# MTL_BaroTact1D_V3.net
KiCad netlist of a schematic drawn in EAGLE
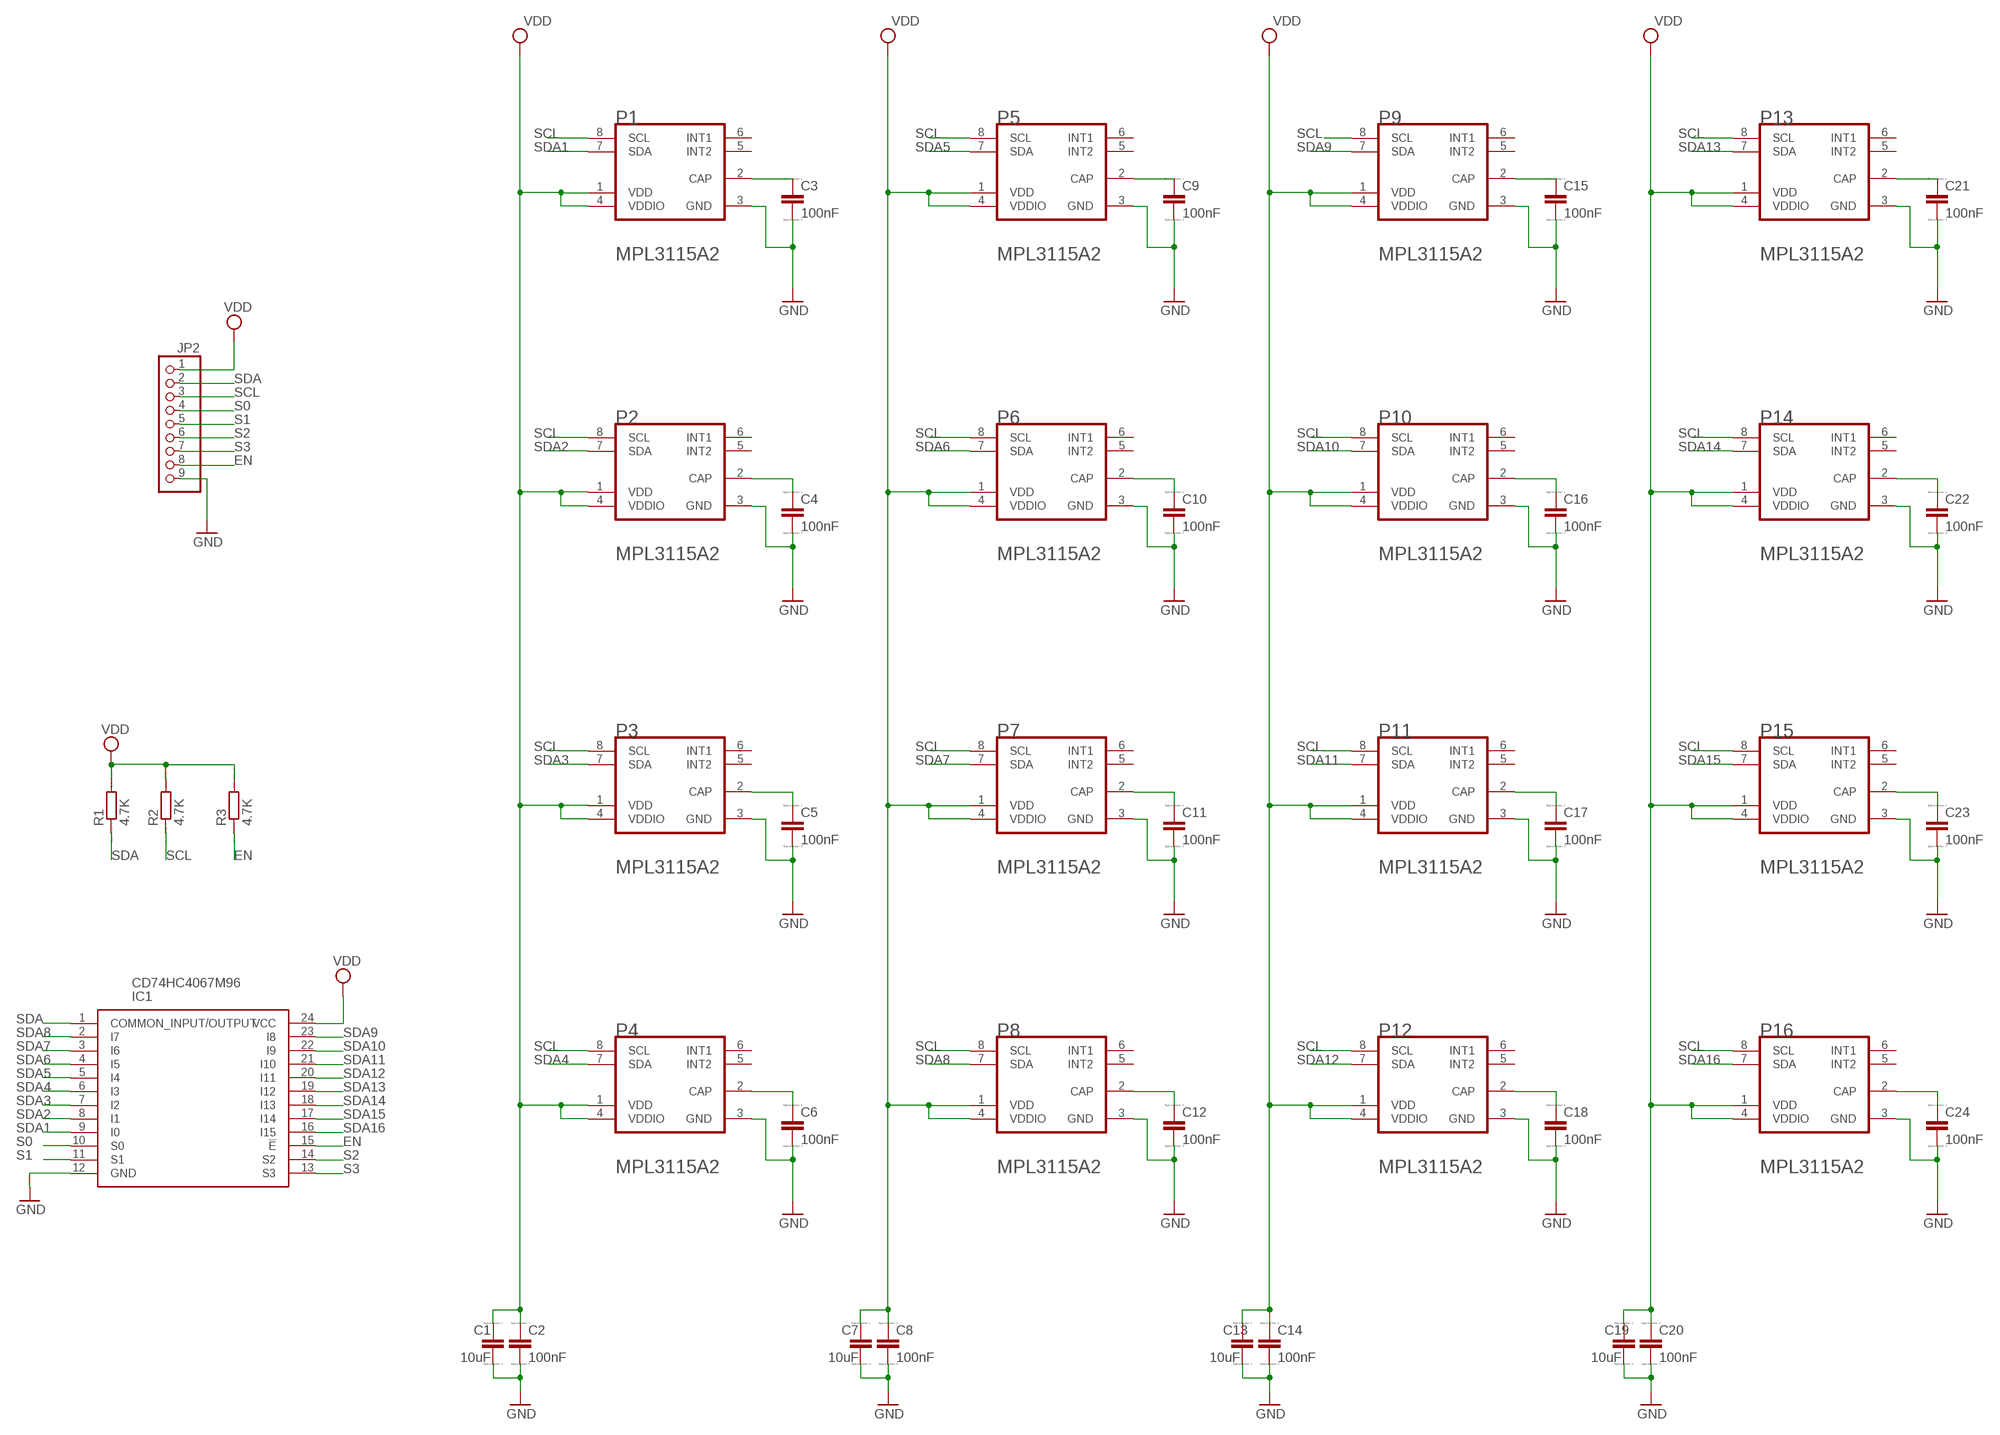
[diagram p0: schematic, sheet 1]

(export (version "E")
  (design (tool "Eeschema 10.0.6"))
  (components
    (comp (ref "C1")
      (value "10uF")
      (footprint "eagle-import:C0603")
      (libsource (lib "eagle-import") (part "CC0603"))
    )
    (comp (ref "C2")
      (value "100nF")
      (footprint "eagle-import:C0603")
      (libsource (lib "eagle-import") (part "CC0603"))
    )
    (comp (ref "C3")
      (value "100nF")
      (footprint "eagle-import:C0603")
      (libsource (lib "eagle-import") (part "CC0603"))
    )
    (comp (ref "C4")
      (value "100nF")
      (footprint "eagle-import:C0603")
      (libsource (lib "eagle-import") (part "CC0603"))
    )
    (comp (ref "C5")
      (value "100nF")
      (footprint "eagle-import:C0603")
      (libsource (lib "eagle-import") (part "CC0603"))
    )
    (comp (ref "C6")
      (value "100nF")
      (footprint "eagle-import:C0603")
      (libsource (lib "eagle-import") (part "CC0603"))
    )
    (comp (ref "C7")
      (value "10uF")
      (footprint "eagle-import:C0603")
      (libsource (lib "eagle-import") (part "CC0603"))
    )
    (comp (ref "C8")
      (value "100nF")
      (footprint "eagle-import:C0603")
      (libsource (lib "eagle-import") (part "CC0603"))
    )
    (comp (ref "C9")
      (value "100nF")
      (footprint "eagle-import:C0603")
      (libsource (lib "eagle-import") (part "CC0603"))
    )
    (comp (ref "C10")
      (value "100nF")
      (footprint "eagle-import:C0603")
      (libsource (lib "eagle-import") (part "CC0603"))
    )
    (comp (ref "C11")
      (value "100nF")
      (footprint "eagle-import:C0603")
      (libsource (lib "eagle-import") (part "CC0603"))
    )
    (comp (ref "C12")
      (value "100nF")
      (footprint "eagle-import:C0603")
      (libsource (lib "eagle-import") (part "CC0603"))
    )
    (comp (ref "C13")
      (value "10uF")
      (footprint "eagle-import:C0603")
      (libsource (lib "eagle-import") (part "CC0603"))
    )
    (comp (ref "C14")
      (value "100nF")
      (footprint "eagle-import:C0603")
      (libsource (lib "eagle-import") (part "CC0603"))
    )
    (comp (ref "C15")
      (value "100nF")
      (footprint "eagle-import:C0603")
      (libsource (lib "eagle-import") (part "CC0603"))
    )
    (comp (ref "C16")
      (value "100nF")
      (footprint "eagle-import:C0603")
      (libsource (lib "eagle-import") (part "CC0603"))
    )
    (comp (ref "C17")
      (value "100nF")
      (footprint "eagle-import:C0603")
      (libsource (lib "eagle-import") (part "CC0603"))
    )
    (comp (ref "C18")
      (value "100nF")
      (footprint "eagle-import:C0603")
      (libsource (lib "eagle-import") (part "CC0603"))
    )
    (comp (ref "C19")
      (value "10uF")
      (footprint "eagle-import:C0603")
      (libsource (lib "eagle-import") (part "CC0603"))
    )
    (comp (ref "C20")
      (value "100nF")
      (footprint "eagle-import:C0603")
      (libsource (lib "eagle-import") (part "CC0603"))
    )
    (comp (ref "C21")
      (value "100nF")
      (footprint "eagle-import:C0603")
      (libsource (lib "eagle-import") (part "CC0603"))
    )
    (comp (ref "C22")
      (value "100nF")
      (footprint "eagle-import:C0603")
      (libsource (lib "eagle-import") (part "CC0603"))
    )
    (comp (ref "C23")
      (value "100nF")
      (footprint "eagle-import:C0603")
      (libsource (lib "eagle-import") (part "CC0603"))
    )
    (comp (ref "C24")
      (value "100nF")
      (footprint "eagle-import:C0603")
      (libsource (lib "eagle-import") (part "CC0603"))
    )
    (comp (ref "IC1")
      (value "CD74HC4067M96")
      (footprint "eagle-import:SOIC127P1030X265-24N")
      (fields (field (name "MOUSER_PART_NUMBER") "595-CD74HC4067M96"))
      (libsource (lib "eagle-import") (part "CD74HC4067M96"))
    )
    (comp (ref "JP2")
      (value "PINHD-1X9")
      (footprint "eagle-import:1X09")
      (libsource (lib "eagle-import") (part "PINHD-1X9"))
    )
    (comp (ref "P1")
      (value "FREESCALE_SEMICONDUCTOR_MPL3115A2FREESCALE_SEMICONDUCTOR_MPL3115A2_0_0")
      (footprint "eagle-import:FREESCALE_SEMICONDUCTOR_MPL3115A2_0")
      (fields (field (name "MF") "Freescale Semiconductor") (field (name "MPN") "MPL3115A2"))
      (libsource (lib "eagle-import") (part "FREESCALE_SEMICONDUCTOR_MPL3115A2FREESCALE_SEMICONDUCTOR_MPL3115A2_0_0"))
    )
    (comp (ref "P2")
      (value "FREESCALE_SEMICONDUCTOR_MPL3115A2FREESCALE_SEMICONDUCTOR_MPL3115A2_0_0")
      (footprint "eagle-import:FREESCALE_SEMICONDUCTOR_MPL3115A2_0")
      (fields (field (name "MF") "Freescale Semiconductor") (field (name "MPN") "MPL3115A2"))
      (libsource (lib "eagle-import") (part "FREESCALE_SEMICONDUCTOR_MPL3115A2FREESCALE_SEMICONDUCTOR_MPL3115A2_0_0"))
    )
    (comp (ref "P3")
      (value "FREESCALE_SEMICONDUCTOR_MPL3115A2FREESCALE_SEMICONDUCTOR_MPL3115A2_0_0")
      (footprint "eagle-import:FREESCALE_SEMICONDUCTOR_MPL3115A2_0")
      (fields (field (name "MF") "Freescale Semiconductor") (field (name "MPN") "MPL3115A2"))
      (libsource (lib "eagle-import") (part "FREESCALE_SEMICONDUCTOR_MPL3115A2FREESCALE_SEMICONDUCTOR_MPL3115A2_0_0"))
    )
    (comp (ref "P4")
      (value "FREESCALE_SEMICONDUCTOR_MPL3115A2FREESCALE_SEMICONDUCTOR_MPL3115A2_0_0")
      (footprint "eagle-import:FREESCALE_SEMICONDUCTOR_MPL3115A2_0")
      (fields (field (name "MF") "Freescale Semiconductor") (field (name "MPN") "MPL3115A2"))
      (libsource (lib "eagle-import") (part "FREESCALE_SEMICONDUCTOR_MPL3115A2FREESCALE_SEMICONDUCTOR_MPL3115A2_0_0"))
    )
    (comp (ref "P5")
      (value "FREESCALE_SEMICONDUCTOR_MPL3115A2FREESCALE_SEMICONDUCTOR_MPL3115A2_0_0")
      (footprint "eagle-import:FREESCALE_SEMICONDUCTOR_MPL3115A2_0")
      (fields (field (name "MF") "Freescale Semiconductor") (field (name "MPN") "MPL3115A2"))
      (libsource (lib "eagle-import") (part "FREESCALE_SEMICONDUCTOR_MPL3115A2FREESCALE_SEMICONDUCTOR_MPL3115A2_0_0"))
    )
    (comp (ref "P6")
      (value "FREESCALE_SEMICONDUCTOR_MPL3115A2FREESCALE_SEMICONDUCTOR_MPL3115A2_0_0")
      (footprint "eagle-import:FREESCALE_SEMICONDUCTOR_MPL3115A2_0")
      (fields (field (name "MF") "Freescale Semiconductor") (field (name "MPN") "MPL3115A2"))
      (libsource (lib "eagle-import") (part "FREESCALE_SEMICONDUCTOR_MPL3115A2FREESCALE_SEMICONDUCTOR_MPL3115A2_0_0"))
    )
    (comp (ref "P7")
      (value "FREESCALE_SEMICONDUCTOR_MPL3115A2FREESCALE_SEMICONDUCTOR_MPL3115A2_0_0")
      (footprint "eagle-import:FREESCALE_SEMICONDUCTOR_MPL3115A2_0")
      (fields (field (name "MF") "Freescale Semiconductor") (field (name "MPN") "MPL3115A2"))
      (libsource (lib "eagle-import") (part "FREESCALE_SEMICONDUCTOR_MPL3115A2FREESCALE_SEMICONDUCTOR_MPL3115A2_0_0"))
    )
    (comp (ref "P8")
      (value "FREESCALE_SEMICONDUCTOR_MPL3115A2FREESCALE_SEMICONDUCTOR_MPL3115A2_0_0")
      (footprint "eagle-import:FREESCALE_SEMICONDUCTOR_MPL3115A2_0")
      (fields (field (name "MF") "Freescale Semiconductor") (field (name "MPN") "MPL3115A2"))
      (libsource (lib "eagle-import") (part "FREESCALE_SEMICONDUCTOR_MPL3115A2FREESCALE_SEMICONDUCTOR_MPL3115A2_0_0"))
    )
    (comp (ref "P9")
      (value "FREESCALE_SEMICONDUCTOR_MPL3115A2FREESCALE_SEMICONDUCTOR_MPL3115A2_0_0")
      (footprint "eagle-import:FREESCALE_SEMICONDUCTOR_MPL3115A2_0")
      (fields (field (name "MF") "Freescale Semiconductor") (field (name "MPN") "MPL3115A2"))
      (libsource (lib "eagle-import") (part "FREESCALE_SEMICONDUCTOR_MPL3115A2FREESCALE_SEMICONDUCTOR_MPL3115A2_0_0"))
    )
    (comp (ref "P10")
      (value "FREESCALE_SEMICONDUCTOR_MPL3115A2FREESCALE_SEMICONDUCTOR_MPL3115A2_0_0")
      (footprint "eagle-import:FREESCALE_SEMICONDUCTOR_MPL3115A2_0")
      (fields (field (name "MF") "Freescale Semiconductor") (field (name "MPN") "MPL3115A2"))
      (libsource (lib "eagle-import") (part "FREESCALE_SEMICONDUCTOR_MPL3115A2FREESCALE_SEMICONDUCTOR_MPL3115A2_0_0"))
    )
    (comp (ref "P11")
      (value "FREESCALE_SEMICONDUCTOR_MPL3115A2FREESCALE_SEMICONDUCTOR_MPL3115A2_0_0")
      (footprint "eagle-import:FREESCALE_SEMICONDUCTOR_MPL3115A2_0")
      (fields (field (name "MF") "Freescale Semiconductor") (field (name "MPN") "MPL3115A2"))
      (libsource (lib "eagle-import") (part "FREESCALE_SEMICONDUCTOR_MPL3115A2FREESCALE_SEMICONDUCTOR_MPL3115A2_0_0"))
    )
    (comp (ref "P12")
      (value "FREESCALE_SEMICONDUCTOR_MPL3115A2FREESCALE_SEMICONDUCTOR_MPL3115A2_0_0")
      (footprint "eagle-import:FREESCALE_SEMICONDUCTOR_MPL3115A2_0")
      (fields (field (name "MF") "Freescale Semiconductor") (field (name "MPN") "MPL3115A2"))
      (libsource (lib "eagle-import") (part "FREESCALE_SEMICONDUCTOR_MPL3115A2FREESCALE_SEMICONDUCTOR_MPL3115A2_0_0"))
    )
    (comp (ref "P13")
      (value "FREESCALE_SEMICONDUCTOR_MPL3115A2FREESCALE_SEMICONDUCTOR_MPL3115A2_0_0")
      (footprint "eagle-import:FREESCALE_SEMICONDUCTOR_MPL3115A2_0")
      (fields (field (name "MF") "Freescale Semiconductor") (field (name "MPN") "MPL3115A2"))
      (libsource (lib "eagle-import") (part "FREESCALE_SEMICONDUCTOR_MPL3115A2FREESCALE_SEMICONDUCTOR_MPL3115A2_0_0"))
    )
    (comp (ref "P14")
      (value "FREESCALE_SEMICONDUCTOR_MPL3115A2FREESCALE_SEMICONDUCTOR_MPL3115A2_0_0")
      (footprint "eagle-import:FREESCALE_SEMICONDUCTOR_MPL3115A2_0")
      (fields (field (name "MF") "Freescale Semiconductor") (field (name "MPN") "MPL3115A2"))
      (libsource (lib "eagle-import") (part "FREESCALE_SEMICONDUCTOR_MPL3115A2FREESCALE_SEMICONDUCTOR_MPL3115A2_0_0"))
    )
    (comp (ref "P15")
      (value "FREESCALE_SEMICONDUCTOR_MPL3115A2FREESCALE_SEMICONDUCTOR_MPL3115A2_0_0")
      (footprint "eagle-import:FREESCALE_SEMICONDUCTOR_MPL3115A2_0")
      (fields (field (name "MF") "Freescale Semiconductor") (field (name "MPN") "MPL3115A2"))
      (libsource (lib "eagle-import") (part "FREESCALE_SEMICONDUCTOR_MPL3115A2FREESCALE_SEMICONDUCTOR_MPL3115A2_0_0"))
    )
    (comp (ref "P16")
      (value "FREESCALE_SEMICONDUCTOR_MPL3115A2FREESCALE_SEMICONDUCTOR_MPL3115A2_0_0")
      (footprint "eagle-import:FREESCALE_SEMICONDUCTOR_MPL3115A2_0")
      (fields (field (name "MF") "Freescale Semiconductor") (field (name "MPN") "MPL3115A2"))
      (libsource (lib "eagle-import") (part "FREESCALE_SEMICONDUCTOR_MPL3115A2FREESCALE_SEMICONDUCTOR_MPL3115A2_0_0"))
    )
    (comp (ref "R1")
      (value "4.7K")
      (footprint "eagle-import:R0603")
      (libsource (lib "eagle-import") (part "RR0603"))
    )
    (comp (ref "R2")
      (value "4.7K")
      (footprint "eagle-import:R0603")
      (libsource (lib "eagle-import") (part "RR0603"))
    )
    (comp (ref "R3")
      (value "4.7K")
      (footprint "eagle-import:R0603")
      (libsource (lib "eagle-import") (part "RR0603"))
    )
  )
  (nets
    (net (code "1") (name "/EN") (class "Default")
      (node (ref "IC1") (pin "15") (pinfunction "~{E}_15") (pintype "bidirectional"))
      (node (ref "JP2") (pin "8") (pinfunction "8_8") (pintype "passive"))
      (node (ref "R3") (pin "1") (pinfunction "1_1") (pintype "passive"))
    )
    (net (code "2") (name "/S0") (class "Default")
      (node (ref "IC1") (pin "10") (pinfunction "S0_10") (pintype "bidirectional"))
      (node (ref "JP2") (pin "4") (pinfunction "4_4") (pintype "passive"))
    )
    (net (code "3") (name "/S1") (class "Default")
      (node (ref "IC1") (pin "11") (pinfunction "S1_11") (pintype "bidirectional"))
      (node (ref "JP2") (pin "5") (pinfunction "5_5") (pintype "passive"))
    )
    (net (code "4") (name "/S2") (class "Default")
      (node (ref "IC1") (pin "14") (pinfunction "S2_14") (pintype "bidirectional"))
      (node (ref "JP2") (pin "6") (pinfunction "6_6") (pintype "passive"))
    )
    (net (code "5") (name "/S3") (class "Default")
      (node (ref "IC1") (pin "13") (pinfunction "S3_13") (pintype "bidirectional"))
      (node (ref "JP2") (pin "7") (pinfunction "7_7") (pintype "passive"))
    )
    (net (code "6") (name "/SCL") (class "Default")
      (node (ref "JP2") (pin "3") (pinfunction "3_3") (pintype "passive"))
      (node (ref "P1") (pin "8") (pinfunction "SCL_8") (pintype "input"))
      (node (ref "P10") (pin "8") (pinfunction "SCL_8") (pintype "input"))
      (node (ref "P11") (pin "8") (pinfunction "SCL_8") (pintype "input"))
      (node (ref "P12") (pin "8") (pinfunction "SCL_8") (pintype "input"))
      (node (ref "P13") (pin "8") (pinfunction "SCL_8") (pintype "input"))
      (node (ref "P14") (pin "8") (pinfunction "SCL_8") (pintype "input"))
      (node (ref "P15") (pin "8") (pinfunction "SCL_8") (pintype "input"))
      (node (ref "P16") (pin "8") (pinfunction "SCL_8") (pintype "input"))
      (node (ref "P2") (pin "8") (pinfunction "SCL_8") (pintype "input"))
      (node (ref "P3") (pin "8") (pinfunction "SCL_8") (pintype "input"))
      (node (ref "P4") (pin "8") (pinfunction "SCL_8") (pintype "input"))
      (node (ref "P5") (pin "8") (pinfunction "SCL_8") (pintype "input"))
      (node (ref "P6") (pin "8") (pinfunction "SCL_8") (pintype "input"))
      (node (ref "P7") (pin "8") (pinfunction "SCL_8") (pintype "input"))
      (node (ref "P8") (pin "8") (pinfunction "SCL_8") (pintype "input"))
      (node (ref "P9") (pin "8") (pinfunction "SCL_8") (pintype "input"))
      (node (ref "R2") (pin "1") (pinfunction "1_1") (pintype "passive"))
    )
    (net (code "7") (name "/SDA") (class "Default")
      (node (ref "IC1") (pin "1") (pinfunction "COMMON_INPUT/OUTPUT_1") (pintype "bidirectional"))
      (node (ref "JP2") (pin "2") (pinfunction "2_2") (pintype "passive"))
      (node (ref "R1") (pin "1") (pinfunction "1_1") (pintype "passive"))
    )
    (net (code "8") (name "/SDA1") (class "Default")
      (node (ref "IC1") (pin "9") (pinfunction "I0_9") (pintype "bidirectional"))
      (node (ref "P1") (pin "7") (pinfunction "SDA_7") (pintype "bidirectional"))
    )
    (net (code "9") (name "/SDA2") (class "Default")
      (node (ref "IC1") (pin "8") (pinfunction "I1_8") (pintype "bidirectional"))
      (node (ref "P2") (pin "7") (pinfunction "SDA_7") (pintype "bidirectional"))
    )
    (net (code "10") (name "/SDA3") (class "Default")
      (node (ref "IC1") (pin "7") (pinfunction "I2_7") (pintype "bidirectional"))
      (node (ref "P3") (pin "7") (pinfunction "SDA_7") (pintype "bidirectional"))
    )
    (net (code "11") (name "/SDA4") (class "Default")
      (node (ref "IC1") (pin "6") (pinfunction "I3_6") (pintype "bidirectional"))
      (node (ref "P4") (pin "7") (pinfunction "SDA_7") (pintype "bidirectional"))
    )
    (net (code "12") (name "/SDA5") (class "Default")
      (node (ref "IC1") (pin "5") (pinfunction "I4_5") (pintype "bidirectional"))
      (node (ref "P5") (pin "7") (pinfunction "SDA_7") (pintype "bidirectional"))
    )
    (net (code "13") (name "/SDA6") (class "Default")
      (node (ref "IC1") (pin "4") (pinfunction "I5_4") (pintype "bidirectional"))
      (node (ref "P6") (pin "7") (pinfunction "SDA_7") (pintype "bidirectional"))
    )
    (net (code "14") (name "/SDA7") (class "Default")
      (node (ref "IC1") (pin "3") (pinfunction "I6_3") (pintype "bidirectional"))
      (node (ref "P7") (pin "7") (pinfunction "SDA_7") (pintype "bidirectional"))
    )
    (net (code "15") (name "/SDA8") (class "Default")
      (node (ref "IC1") (pin "2") (pinfunction "I7_2") (pintype "bidirectional"))
      (node (ref "P8") (pin "7") (pinfunction "SDA_7") (pintype "bidirectional"))
    )
    (net (code "16") (name "/SDA9") (class "Default")
      (node (ref "IC1") (pin "23") (pinfunction "I8_23") (pintype "bidirectional"))
      (node (ref "P9") (pin "7") (pinfunction "SDA_7") (pintype "bidirectional"))
    )
    (net (code "17") (name "/SDA10") (class "Default")
      (node (ref "IC1") (pin "22") (pinfunction "I9_22") (pintype "bidirectional"))
      (node (ref "P10") (pin "7") (pinfunction "SDA_7") (pintype "bidirectional"))
    )
    (net (code "18") (name "/SDA11") (class "Default")
      (node (ref "IC1") (pin "21") (pinfunction "I10_21") (pintype "bidirectional"))
      (node (ref "P11") (pin "7") (pinfunction "SDA_7") (pintype "bidirectional"))
    )
    (net (code "19") (name "/SDA12") (class "Default")
      (node (ref "IC1") (pin "20") (pinfunction "I11_20") (pintype "bidirectional"))
      (node (ref "P12") (pin "7") (pinfunction "SDA_7") (pintype "bidirectional"))
    )
    (net (code "20") (name "/SDA13") (class "Default")
      (node (ref "IC1") (pin "19") (pinfunction "I12_19") (pintype "bidirectional"))
      (node (ref "P13") (pin "7") (pinfunction "SDA_7") (pintype "bidirectional"))
    )
    (net (code "21") (name "/SDA14") (class "Default")
      (node (ref "IC1") (pin "18") (pinfunction "I13_18") (pintype "bidirectional"))
      (node (ref "P14") (pin "7") (pinfunction "SDA_7") (pintype "bidirectional"))
    )
    (net (code "22") (name "/SDA15") (class "Default")
      (node (ref "IC1") (pin "17") (pinfunction "I14_17") (pintype "bidirectional"))
      (node (ref "P15") (pin "7") (pinfunction "SDA_7") (pintype "bidirectional"))
    )
    (net (code "23") (name "/SDA16") (class "Default")
      (node (ref "IC1") (pin "16") (pinfunction "I15_16") (pintype "bidirectional"))
      (node (ref "P16") (pin "7") (pinfunction "SDA_7") (pintype "bidirectional"))
    )
    (net (code "24") (name "GND") (class "Default")
      (node (ref "C1") (pin "2") (pinfunction "2_2") (pintype "passive"))
      (node (ref "C10") (pin "2") (pinfunction "2_2") (pintype "passive"))
      (node (ref "C11") (pin "2") (pinfunction "2_2") (pintype "passive"))
      (node (ref "C12") (pin "2") (pinfunction "2_2") (pintype "passive"))
      (node (ref "C13") (pin "2") (pinfunction "2_2") (pintype "passive"))
      (node (ref "C14") (pin "2") (pinfunction "2_2") (pintype "passive"))
      (node (ref "C15") (pin "2") (pinfunction "2_2") (pintype "passive"))
      (node (ref "C16") (pin "2") (pinfunction "2_2") (pintype "passive"))
      (node (ref "C17") (pin "2") (pinfunction "2_2") (pintype "passive"))
      (node (ref "C18") (pin "2") (pinfunction "2_2") (pintype "passive"))
      (node (ref "C19") (pin "2") (pinfunction "2_2") (pintype "passive"))
      (node (ref "C2") (pin "2") (pinfunction "2_2") (pintype "passive"))
      (node (ref "C20") (pin "2") (pinfunction "2_2") (pintype "passive"))
      (node (ref "C21") (pin "2") (pinfunction "2_2") (pintype "passive"))
      (node (ref "C22") (pin "2") (pinfunction "2_2") (pintype "passive"))
      (node (ref "C23") (pin "2") (pinfunction "2_2") (pintype "passive"))
      (node (ref "C24") (pin "2") (pinfunction "2_2") (pintype "passive"))
      (node (ref "C3") (pin "2") (pinfunction "2_2") (pintype "passive"))
      (node (ref "C4") (pin "2") (pinfunction "2_2") (pintype "passive"))
      (node (ref "C5") (pin "2") (pinfunction "2_2") (pintype "passive"))
      (node (ref "C6") (pin "2") (pinfunction "2_2") (pintype "passive"))
      (node (ref "C7") (pin "2") (pinfunction "2_2") (pintype "passive"))
      (node (ref "C8") (pin "2") (pinfunction "2_2") (pintype "passive"))
      (node (ref "C9") (pin "2") (pinfunction "2_2") (pintype "passive"))
      (node (ref "IC1") (pin "12") (pinfunction "GND_12") (pintype "bidirectional"))
      (node (ref "JP2") (pin "9") (pinfunction "9_9") (pintype "passive"))
      (node (ref "P1") (pin "3") (pinfunction "GND_3") (pintype "power_in"))
      (node (ref "P10") (pin "3") (pinfunction "GND_3") (pintype "power_in"))
      (node (ref "P11") (pin "3") (pinfunction "GND_3") (pintype "power_in"))
      (node (ref "P12") (pin "3") (pinfunction "GND_3") (pintype "power_in"))
      (node (ref "P13") (pin "3") (pinfunction "GND_3") (pintype "power_in"))
      (node (ref "P14") (pin "3") (pinfunction "GND_3") (pintype "power_in"))
      (node (ref "P15") (pin "3") (pinfunction "GND_3") (pintype "power_in"))
      (node (ref "P16") (pin "3") (pinfunction "GND_3") (pintype "power_in"))
      (node (ref "P2") (pin "3") (pinfunction "GND_3") (pintype "power_in"))
      (node (ref "P3") (pin "3") (pinfunction "GND_3") (pintype "power_in"))
      (node (ref "P4") (pin "3") (pinfunction "GND_3") (pintype "power_in"))
      (node (ref "P5") (pin "3") (pinfunction "GND_3") (pintype "power_in"))
      (node (ref "P6") (pin "3") (pinfunction "GND_3") (pintype "power_in"))
      (node (ref "P7") (pin "3") (pinfunction "GND_3") (pintype "power_in"))
      (node (ref "P8") (pin "3") (pinfunction "GND_3") (pintype "power_in"))
      (node (ref "P9") (pin "3") (pinfunction "GND_3") (pintype "power_in"))
    )
    (net (code "25") (name "Net-(P1-CAP)") (class "Default")
      (node (ref "C3") (pin "1") (pinfunction "1_1") (pintype "passive"))
      (node (ref "P1") (pin "2") (pinfunction "CAP_2") (pintype "passive"))
    )
    (net (code "26") (name "Net-(P2-CAP)") (class "Default")
      (node (ref "C4") (pin "1") (pinfunction "1_1") (pintype "passive"))
      (node (ref "P2") (pin "2") (pinfunction "CAP_2") (pintype "passive"))
    )
    (net (code "27") (name "Net-(P3-CAP)") (class "Default")
      (node (ref "C5") (pin "1") (pinfunction "1_1") (pintype "passive"))
      (node (ref "P3") (pin "2") (pinfunction "CAP_2") (pintype "passive"))
    )
    (net (code "28") (name "Net-(P4-CAP)") (class "Default")
      (node (ref "C6") (pin "1") (pinfunction "1_1") (pintype "passive"))
      (node (ref "P4") (pin "2") (pinfunction "CAP_2") (pintype "passive"))
    )
    (net (code "29") (name "Net-(P5-CAP)") (class "Default")
      (node (ref "C9") (pin "1") (pinfunction "1_1") (pintype "passive"))
      (node (ref "P5") (pin "2") (pinfunction "CAP_2") (pintype "passive"))
    )
    (net (code "30") (name "Net-(P6-CAP)") (class "Default")
      (node (ref "C10") (pin "1") (pinfunction "1_1") (pintype "passive"))
      (node (ref "P6") (pin "2") (pinfunction "CAP_2") (pintype "passive"))
    )
    (net (code "31") (name "Net-(P7-CAP)") (class "Default")
      (node (ref "C11") (pin "1") (pinfunction "1_1") (pintype "passive"))
      (node (ref "P7") (pin "2") (pinfunction "CAP_2") (pintype "passive"))
    )
    (net (code "32") (name "Net-(P8-CAP)") (class "Default")
      (node (ref "C12") (pin "1") (pinfunction "1_1") (pintype "passive"))
      (node (ref "P8") (pin "2") (pinfunction "CAP_2") (pintype "passive"))
    )
    (net (code "33") (name "Net-(P9-CAP)") (class "Default")
      (node (ref "C15") (pin "1") (pinfunction "1_1") (pintype "passive"))
      (node (ref "P9") (pin "2") (pinfunction "CAP_2") (pintype "passive"))
    )
    (net (code "34") (name "Net-(P10-CAP)") (class "Default")
      (node (ref "C16") (pin "1") (pinfunction "1_1") (pintype "passive"))
      (node (ref "P10") (pin "2") (pinfunction "CAP_2") (pintype "passive"))
    )
    (net (code "35") (name "Net-(P11-CAP)") (class "Default")
      (node (ref "C17") (pin "1") (pinfunction "1_1") (pintype "passive"))
      (node (ref "P11") (pin "2") (pinfunction "CAP_2") (pintype "passive"))
    )
    (net (code "36") (name "Net-(P12-CAP)") (class "Default")
      (node (ref "C18") (pin "1") (pinfunction "1_1") (pintype "passive"))
      (node (ref "P12") (pin "2") (pinfunction "CAP_2") (pintype "passive"))
    )
    (net (code "37") (name "Net-(P13-CAP)") (class "Default")
      (node (ref "C21") (pin "1") (pinfunction "1_1") (pintype "passive"))
      (node (ref "P13") (pin "2") (pinfunction "CAP_2") (pintype "passive"))
    )
    (net (code "38") (name "Net-(P14-CAP)") (class "Default")
      (node (ref "C22") (pin "1") (pinfunction "1_1") (pintype "passive"))
      (node (ref "P14") (pin "2") (pinfunction "CAP_2") (pintype "passive"))
    )
    (net (code "39") (name "Net-(P15-CAP)") (class "Default")
      (node (ref "C23") (pin "1") (pinfunction "1_1") (pintype "passive"))
      (node (ref "P15") (pin "2") (pinfunction "CAP_2") (pintype "passive"))
    )
    (net (code "40") (name "Net-(P16-CAP)") (class "Default")
      (node (ref "C24") (pin "1") (pinfunction "1_1") (pintype "passive"))
      (node (ref "P16") (pin "2") (pinfunction "CAP_2") (pintype "passive"))
    )
    (net (code "41") (name "VDD") (class "Default")
      (node (ref "C1") (pin "1") (pinfunction "1_1") (pintype "passive"))
      (node (ref "C13") (pin "1") (pinfunction "1_1") (pintype "passive"))
      (node (ref "C14") (pin "1") (pinfunction "1_1") (pintype "passive"))
      (node (ref "C19") (pin "1") (pinfunction "1_1") (pintype "passive"))
      (node (ref "C2") (pin "1") (pinfunction "1_1") (pintype "passive"))
      (node (ref "C20") (pin "1") (pinfunction "1_1") (pintype "passive"))
      (node (ref "C7") (pin "1") (pinfunction "1_1") (pintype "passive"))
      (node (ref "C8") (pin "1") (pinfunction "1_1") (pintype "passive"))
      (node (ref "IC1") (pin "24") (pinfunction "VCC_24") (pintype "bidirectional"))
      (node (ref "JP2") (pin "1") (pinfunction "1_1") (pintype "passive"))
      (node (ref "P1") (pin "1") (pinfunction "VDD_1") (pintype "power_in"))
      (node (ref "P1") (pin "4") (pinfunction "VDDIO_4") (pintype "power_in"))
      (node (ref "P10") (pin "1") (pinfunction "VDD_1") (pintype "power_in"))
      (node (ref "P10") (pin "4") (pinfunction "VDDIO_4") (pintype "power_in"))
      (node (ref "P11") (pin "1") (pinfunction "VDD_1") (pintype "power_in"))
      (node (ref "P11") (pin "4") (pinfunction "VDDIO_4") (pintype "power_in"))
      (node (ref "P12") (pin "1") (pinfunction "VDD_1") (pintype "power_in"))
      (node (ref "P12") (pin "4") (pinfunction "VDDIO_4") (pintype "power_in"))
      (node (ref "P13") (pin "1") (pinfunction "VDD_1") (pintype "power_in"))
      (node (ref "P13") (pin "4") (pinfunction "VDDIO_4") (pintype "power_in"))
      (node (ref "P14") (pin "1") (pinfunction "VDD_1") (pintype "power_in"))
      (node (ref "P14") (pin "4") (pinfunction "VDDIO_4") (pintype "power_in"))
      (node (ref "P15") (pin "1") (pinfunction "VDD_1") (pintype "power_in"))
      (node (ref "P15") (pin "4") (pinfunction "VDDIO_4") (pintype "power_in"))
      (node (ref "P16") (pin "1") (pinfunction "VDD_1") (pintype "power_in"))
      (node (ref "P16") (pin "4") (pinfunction "VDDIO_4") (pintype "power_in"))
      (node (ref "P2") (pin "1") (pinfunction "VDD_1") (pintype "power_in"))
      (node (ref "P2") (pin "4") (pinfunction "VDDIO_4") (pintype "power_in"))
      (node (ref "P3") (pin "1") (pinfunction "VDD_1") (pintype "power_in"))
      (node (ref "P3") (pin "4") (pinfunction "VDDIO_4") (pintype "power_in"))
      (node (ref "P4") (pin "1") (pinfunction "VDD_1") (pintype "power_in"))
      (node (ref "P4") (pin "4") (pinfunction "VDDIO_4") (pintype "power_in"))
      (node (ref "P5") (pin "1") (pinfunction "VDD_1") (pintype "power_in"))
      (node (ref "P5") (pin "4") (pinfunction "VDDIO_4") (pintype "power_in"))
      (node (ref "P6") (pin "1") (pinfunction "VDD_1") (pintype "power_in"))
      (node (ref "P6") (pin "4") (pinfunction "VDDIO_4") (pintype "power_in"))
      (node (ref "P7") (pin "1") (pinfunction "VDD_1") (pintype "power_in"))
      (node (ref "P7") (pin "4") (pinfunction "VDDIO_4") (pintype "power_in"))
      (node (ref "P8") (pin "1") (pinfunction "VDD_1") (pintype "power_in"))
      (node (ref "P8") (pin "4") (pinfunction "VDDIO_4") (pintype "power_in"))
      (node (ref "P9") (pin "1") (pinfunction "VDD_1") (pintype "power_in"))
      (node (ref "P9") (pin "4") (pinfunction "VDDIO_4") (pintype "power_in"))
      (node (ref "R1") (pin "2") (pinfunction "2_2") (pintype "passive"))
      (node (ref "R2") (pin "2") (pinfunction "2_2") (pintype "passive"))
      (node (ref "R3") (pin "2") (pinfunction "2_2") (pintype "passive"))
    )
    (net (code "42") (name "unconnected-(P1-INT1-Pad6)") (class "Default")
      (node (ref "P1") (pin "6") (pinfunction "INT1_6") (pintype "output"))
    )
    (net (code "43") (name "unconnected-(P1-INT2-Pad5)") (class "Default")
      (node (ref "P1") (pin "5") (pinfunction "INT2_5") (pintype "output"))
    )
    (net (code "44") (name "unconnected-(P2-INT1-Pad6)") (class "Default")
      (node (ref "P2") (pin "6") (pinfunction "INT1_6") (pintype "output"))
    )
    (net (code "45") (name "unconnected-(P2-INT2-Pad5)") (class "Default")
      (node (ref "P2") (pin "5") (pinfunction "INT2_5") (pintype "output"))
    )
    (net (code "46") (name "unconnected-(P3-INT1-Pad6)") (class "Default")
      (node (ref "P3") (pin "6") (pinfunction "INT1_6") (pintype "output"))
    )
    (net (code "47") (name "unconnected-(P3-INT2-Pad5)") (class "Default")
      (node (ref "P3") (pin "5") (pinfunction "INT2_5") (pintype "output"))
    )
    (net (code "48") (name "unconnected-(P4-INT1-Pad6)") (class "Default")
      (node (ref "P4") (pin "6") (pinfunction "INT1_6") (pintype "output"))
    )
    (net (code "49") (name "unconnected-(P4-INT2-Pad5)") (class "Default")
      (node (ref "P4") (pin "5") (pinfunction "INT2_5") (pintype "output"))
    )
    (net (code "50") (name "unconnected-(P5-INT1-Pad6)") (class "Default")
      (node (ref "P5") (pin "6") (pinfunction "INT1_6") (pintype "output"))
    )
    (net (code "51") (name "unconnected-(P5-INT2-Pad5)") (class "Default")
      (node (ref "P5") (pin "5") (pinfunction "INT2_5") (pintype "output"))
    )
    (net (code "52") (name "unconnected-(P6-INT1-Pad6)") (class "Default")
      (node (ref "P6") (pin "6") (pinfunction "INT1_6") (pintype "output"))
    )
    (net (code "53") (name "unconnected-(P6-INT2-Pad5)") (class "Default")
      (node (ref "P6") (pin "5") (pinfunction "INT2_5") (pintype "output"))
    )
    (net (code "54") (name "unconnected-(P7-INT1-Pad6)") (class "Default")
      (node (ref "P7") (pin "6") (pinfunction "INT1_6") (pintype "output"))
    )
    (net (code "55") (name "unconnected-(P7-INT2-Pad5)") (class "Default")
      (node (ref "P7") (pin "5") (pinfunction "INT2_5") (pintype "output"))
    )
    (net (code "56") (name "unconnected-(P8-INT1-Pad6)") (class "Default")
      (node (ref "P8") (pin "6") (pinfunction "INT1_6") (pintype "output"))
    )
    (net (code "57") (name "unconnected-(P8-INT2-Pad5)") (class "Default")
      (node (ref "P8") (pin "5") (pinfunction "INT2_5") (pintype "output"))
    )
    (net (code "58") (name "unconnected-(P9-INT1-Pad6)") (class "Default")
      (node (ref "P9") (pin "6") (pinfunction "INT1_6") (pintype "output"))
    )
    (net (code "59") (name "unconnected-(P9-INT2-Pad5)") (class "Default")
      (node (ref "P9") (pin "5") (pinfunction "INT2_5") (pintype "output"))
    )
    (net (code "60") (name "unconnected-(P10-INT1-Pad6)") (class "Default")
      (node (ref "P10") (pin "6") (pinfunction "INT1_6") (pintype "output"))
    )
    (net (code "61") (name "unconnected-(P10-INT2-Pad5)") (class "Default")
      (node (ref "P10") (pin "5") (pinfunction "INT2_5") (pintype "output"))
    )
    (net (code "62") (name "unconnected-(P11-INT1-Pad6)") (class "Default")
      (node (ref "P11") (pin "6") (pinfunction "INT1_6") (pintype "output"))
    )
    (net (code "63") (name "unconnected-(P11-INT2-Pad5)") (class "Default")
      (node (ref "P11") (pin "5") (pinfunction "INT2_5") (pintype "output"))
    )
    (net (code "64") (name "unconnected-(P12-INT1-Pad6)") (class "Default")
      (node (ref "P12") (pin "6") (pinfunction "INT1_6") (pintype "output"))
    )
    (net (code "65") (name "unconnected-(P12-INT2-Pad5)") (class "Default")
      (node (ref "P12") (pin "5") (pinfunction "INT2_5") (pintype "output"))
    )
    (net (code "66") (name "unconnected-(P13-INT1-Pad6)") (class "Default")
      (node (ref "P13") (pin "6") (pinfunction "INT1_6") (pintype "output"))
    )
    (net (code "67") (name "unconnected-(P13-INT2-Pad5)") (class "Default")
      (node (ref "P13") (pin "5") (pinfunction "INT2_5") (pintype "output"))
    )
    (net (code "68") (name "unconnected-(P14-INT1-Pad6)") (class "Default")
      (node (ref "P14") (pin "6") (pinfunction "INT1_6") (pintype "output"))
    )
    (net (code "69") (name "unconnected-(P14-INT2-Pad5)") (class "Default")
      (node (ref "P14") (pin "5") (pinfunction "INT2_5") (pintype "output"))
    )
    (net (code "70") (name "unconnected-(P15-INT1-Pad6)") (class "Default")
      (node (ref "P15") (pin "6") (pinfunction "INT1_6") (pintype "output"))
    )
    (net (code "71") (name "unconnected-(P15-INT2-Pad5)") (class "Default")
      (node (ref "P15") (pin "5") (pinfunction "INT2_5") (pintype "output"))
    )
    (net (code "72") (name "unconnected-(P16-INT1-Pad6)") (class "Default")
      (node (ref "P16") (pin "6") (pinfunction "INT1_6") (pintype "output"))
    )
    (net (code "73") (name "unconnected-(P16-INT2-Pad5)") (class "Default")
      (node (ref "P16") (pin "5") (pinfunction "INT2_5") (pintype "output"))
    )
  )
)
